# teiler10e7V3.net
KiCad netlist of a schematic drawn in EAGLE
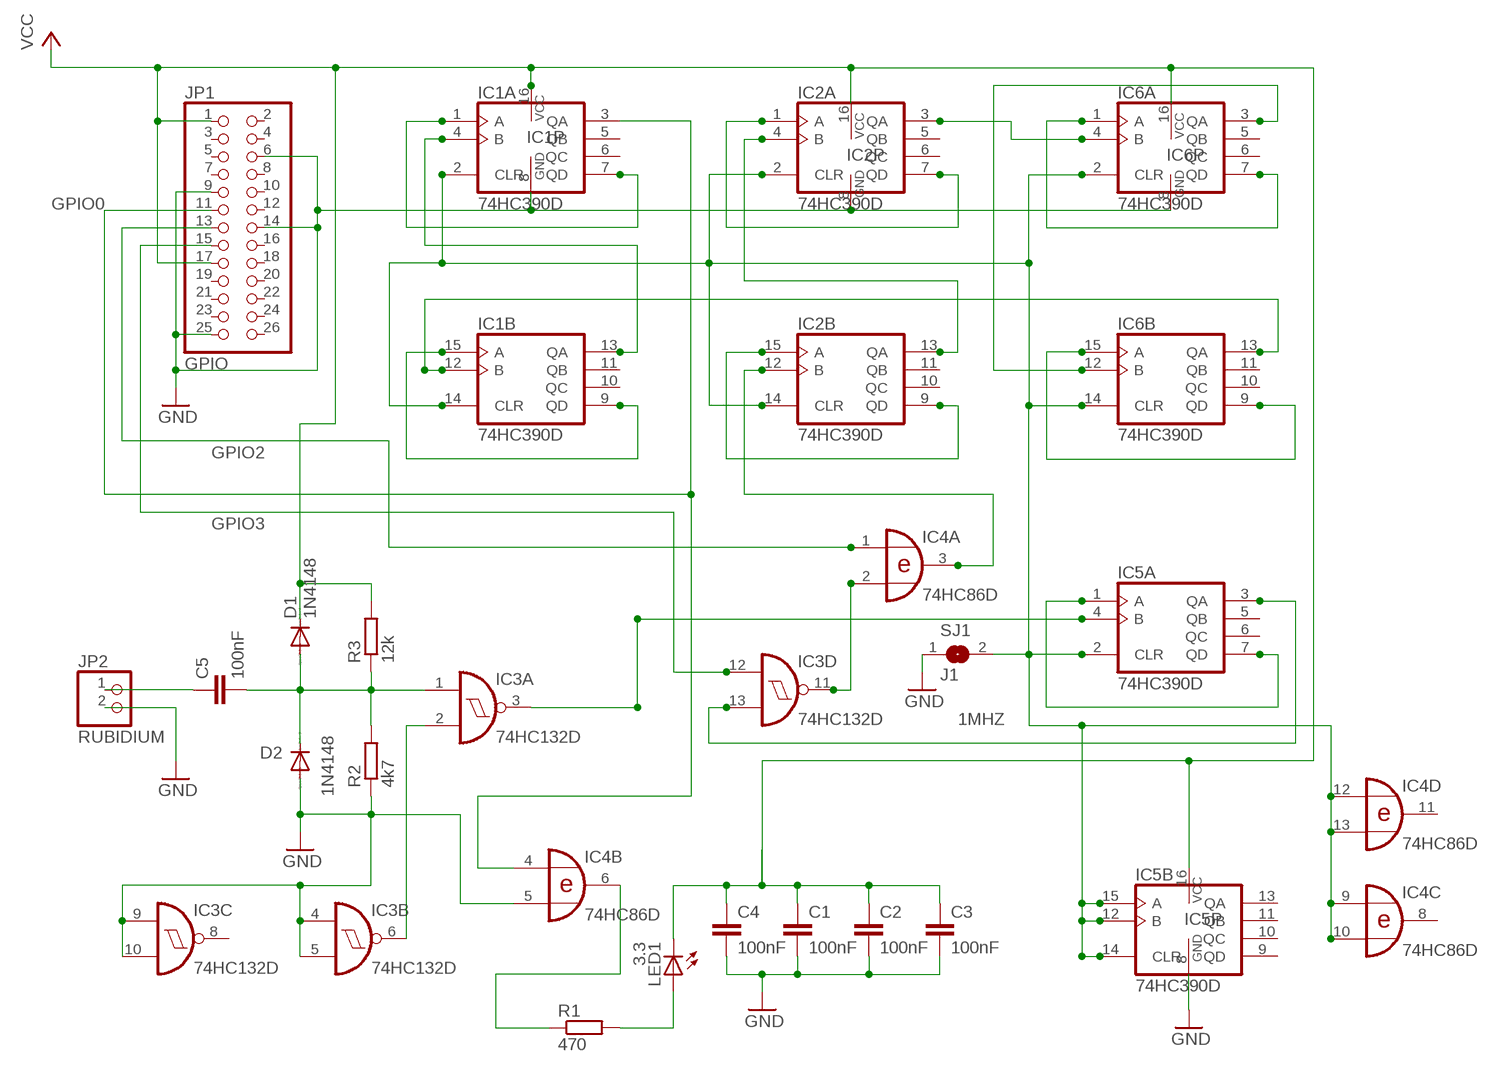
[diagram p0: schematic, sheet 1]

(export (version "E")
  (design (tool "Eeschema 10.0.6"))
  (components
    (comp (ref "C1")
      (value "100nF")
      (footprint "eagle-import:C025-025X050")
      (libsource (lib "eagle-import") (part "C-EU025-025X050"))
    )
    (comp (ref "C2")
      (value "100nF")
      (footprint "eagle-import:C025-025X050")
      (libsource (lib "eagle-import") (part "C-EU025-025X050"))
    )
    (comp (ref "C3")
      (value "100nF")
      (footprint "eagle-import:C025-025X050")
      (libsource (lib "eagle-import") (part "C-EU025-025X050"))
    )
    (comp (ref "C4")
      (value "100nF")
      (footprint "eagle-import:C025-025X050")
      (libsource (lib "eagle-import") (part "C-EU025-025X050"))
    )
    (comp (ref "C5")
      (value "100nF")
      (footprint "eagle-import:C025-025X050")
      (libsource (lib "eagle-import") (part "C-EU025-025X050"))
    )
    (comp (ref "D1")
      (value "1N4148")
      (footprint "eagle-import:DO35-7")
      (libsource (lib "eagle-import") (part "1N4148DO35-7"))
    )
    (comp (ref "D2")
      (value "1N4148")
      (footprint "eagle-import:DO35-7")
      (libsource (lib "eagle-import") (part "1N4148DO35-7"))
    )
    (comp (ref "IC1")
      (value "74HC390D")
      (footprint "eagle-import:SO16")
      (libsource (lib "eagle-import") (part "74390DHC"))
    )
    (comp (ref "IC2")
      (value "74HC390D")
      (footprint "eagle-import:SO16")
      (libsource (lib "eagle-import") (part "74390DHC"))
    )
    (comp (ref "IC3")
      (value "74HC132D")
      (footprint "eagle-import:SO14")
      (libsource (lib "eagle-import") (part "74132DHC"))
    )
    (comp (ref "IC4")
      (value "74HC86D")
      (footprint "eagle-import:SO14")
      (libsource (lib "eagle-import") (part "7486DHC"))
    )
    (comp (ref "IC5")
      (value "74HC390D")
      (footprint "eagle-import:SO16")
      (libsource (lib "eagle-import") (part "74390DHC"))
    )
    (comp (ref "IC6")
      (value "74HC390D")
      (footprint "eagle-import:SO16")
      (libsource (lib "eagle-import") (part "74390DHC"))
    )
    (comp (ref "JP1")
      (value "GPIO")
      (footprint "eagle-import:2X13")
      (libsource (lib "eagle-import") (part "PINHD-2X13"))
    )
    (comp (ref "JP2")
      (value "RUBIDIUM")
      (footprint "eagle-import:1X02_90")
      (libsource (lib "eagle-import") (part "PINHD-1X2/90"))
    )
    (comp (ref "LED1")
      (value "3.3")
      (footprint "eagle-import:LED3MM")
      (libsource (lib "eagle-import") (part "LED3MM"))
    )
    (comp (ref "R1")
      (value "470")
      (footprint "eagle-import:0207_10")
      (libsource (lib "eagle-import") (part "R-EU_0207/10"))
    )
    (comp (ref "R2")
      (value "4k7")
      (footprint "eagle-import:0207_10")
      (libsource (lib "eagle-import") (part "R-EU_0207/10"))
    )
    (comp (ref "R3")
      (value "12k")
      (footprint "eagle-import:0207_10")
      (libsource (lib "eagle-import") (part "R-EU_0207/10"))
    )
    (comp (ref "SJ1")
      (value "J1")
      (footprint "eagle-import:SJW")
      (libsource (lib "eagle-import") (part "SJW"))
    )
  )
  (nets
    (net (code "1") (name "/1MHZ") (class "Default")
      (node (ref "IC3") (pin "13") (pinfunction "I1_13") (pintype "input"))
      (node (ref "IC5") (pin "3") (pinfunction "QA_3") (pintype "output"))
    )
    (net (code "2") (name "/GPIO0") (class "Default")
      (node (ref "IC1") (pin "3") (pinfunction "QA_3") (pintype "output"))
      (node (ref "IC4") (pin "4") (pinfunction "I0_4") (pintype "input"))
      (node (ref "JP1") (pin "11") (pinfunction "11_11") (pintype "passive"))
    )
    (net (code "3") (name "/GPIO2") (class "Default")
      (node (ref "IC4") (pin "1") (pinfunction "I0_1") (pintype "input"))
      (node (ref "JP1") (pin "13") (pinfunction "13_13") (pintype "passive"))
    )
    (net (code "4") (name "/GPIO3") (class "Default")
      (node (ref "IC3") (pin "12") (pinfunction "I0_12") (pintype "input"))
      (node (ref "JP1") (pin "15") (pinfunction "15_15") (pintype "passive"))
    )
    (net (code "5") (name "GND") (class "Default")
      (node (ref "C1") (pin "2") (pinfunction "2_2") (pintype "passive"))
      (node (ref "C2") (pin "2") (pinfunction "2_2") (pintype "passive"))
      (node (ref "C3") (pin "2") (pinfunction "2_2") (pintype "passive"))
      (node (ref "C4") (pin "2") (pinfunction "2_2") (pintype "passive"))
      (node (ref "D2") (pin "A") (pinfunction "A_A") (pintype "passive"))
      (node (ref "IC1") (pin "8") (pinfunction "GND_8") (pintype "power_in"))
      (node (ref "IC2") (pin "8") (pinfunction "GND_8") (pintype "power_in"))
      (node (ref "IC3") (pin "10") (pinfunction "I1_10") (pintype "input"))
      (node (ref "IC3") (pin "4") (pinfunction "I0_4") (pintype "input"))
      (node (ref "IC3") (pin "5") (pinfunction "I1_5") (pintype "input"))
      (node (ref "IC3") (pin "9") (pinfunction "I0_9") (pintype "input"))
      (node (ref "IC4") (pin "5") (pinfunction "I1_5") (pintype "input"))
      (node (ref "IC5") (pin "8") (pinfunction "GND_8") (pintype "power_in"))
      (node (ref "IC6") (pin "8") (pinfunction "GND_8") (pintype "power_in"))
      (node (ref "JP1") (pin "14") (pinfunction "14_14") (pintype "passive"))
      (node (ref "JP1") (pin "25") (pinfunction "25_25") (pintype "passive"))
      (node (ref "JP1") (pin "6") (pinfunction "6_6") (pintype "passive"))
      (node (ref "JP1") (pin "9") (pinfunction "9_9") (pintype "passive"))
      (node (ref "JP2") (pin "2") (pinfunction "2_2") (pintype "passive"))
      (node (ref "R2") (pin "1") (pinfunction "1_1") (pintype "passive"))
      (node (ref "SJ1") (pin "1") (pinfunction "1_1") (pintype "passive"))
    )
    (net (code "6") (name "Net-(C5-Pad1)") (class "Default")
      (node (ref "C5") (pin "1") (pinfunction "1_1") (pintype "passive"))
      (node (ref "JP2") (pin "1") (pinfunction "1_1") (pintype "passive"))
    )
    (net (code "7") (name "Net-(IC1A-A)") (class "Default")
      (node (ref "IC1") (pin "1") (pinfunction "A_1") (pintype "input"))
      (node (ref "IC1") (pin "7") (pinfunction "QD_7") (pintype "output"))
    )
    (net (code "8") (name "Net-(IC1A-B)") (class "Default")
      (node (ref "IC1") (pin "13") (pinfunction "QA_13") (pintype "output"))
      (node (ref "IC1") (pin "4") (pinfunction "B_4") (pintype "input"))
    )
    (net (code "9") (name "Net-(IC1A-CLR)") (class "Default")
      (node (ref "IC1") (pin "14") (pinfunction "CLR_14") (pintype "input"))
      (node (ref "IC1") (pin "2") (pinfunction "CLR_2") (pintype "input"))
      (node (ref "IC2") (pin "14") (pinfunction "CLR_14") (pintype "input"))
      (node (ref "IC2") (pin "2") (pinfunction "CLR_2") (pintype "input"))
      (node (ref "IC4") (pin "10") (pinfunction "I1_10") (pintype "input"))
      (node (ref "IC4") (pin "12") (pinfunction "I0_12") (pintype "input"))
      (node (ref "IC4") (pin "13") (pinfunction "I1_13") (pintype "input"))
      (node (ref "IC4") (pin "9") (pinfunction "I0_9") (pintype "input"))
      (node (ref "IC5") (pin "12") (pinfunction "B_12") (pintype "input"))
      (node (ref "IC5") (pin "14") (pinfunction "CLR_14") (pintype "input"))
      (node (ref "IC5") (pin "15") (pinfunction "A_15") (pintype "input"))
      (node (ref "IC5") (pin "2") (pinfunction "CLR_2") (pintype "input"))
      (node (ref "IC6") (pin "14") (pinfunction "CLR_14") (pintype "input"))
      (node (ref "IC6") (pin "2") (pinfunction "CLR_2") (pintype "input"))
      (node (ref "SJ1") (pin "2") (pinfunction "2_2") (pintype "passive"))
    )
    (net (code "10") (name "Net-(IC1B-A)") (class "Default")
      (node (ref "IC1") (pin "15") (pinfunction "A_15") (pintype "input"))
      (node (ref "IC1") (pin "9") (pinfunction "QD_9") (pintype "output"))
    )
    (net (code "11") (name "Net-(IC1B-B)") (class "Default")
      (node (ref "IC1") (pin "12") (pinfunction "B_12") (pintype "input"))
      (node (ref "IC6") (pin "13") (pinfunction "QA_13") (pintype "output"))
    )
    (net (code "12") (name "Net-(IC2A-A)") (class "Default")
      (node (ref "IC2") (pin "1") (pinfunction "A_1") (pintype "input"))
      (node (ref "IC2") (pin "7") (pinfunction "QD_7") (pintype "output"))
    )
    (net (code "13") (name "Net-(IC2A-B)") (class "Default")
      (node (ref "IC2") (pin "13") (pinfunction "QA_13") (pintype "output"))
      (node (ref "IC2") (pin "4") (pinfunction "B_4") (pintype "input"))
    )
    (net (code "14") (name "Net-(IC2A-QA)") (class "Default")
      (node (ref "IC2") (pin "3") (pinfunction "QA_3") (pintype "output"))
      (node (ref "IC6") (pin "4") (pinfunction "B_4") (pintype "input"))
    )
    (net (code "15") (name "Net-(IC2B-A)") (class "Default")
      (node (ref "IC2") (pin "15") (pinfunction "A_15") (pintype "input"))
      (node (ref "IC2") (pin "9") (pinfunction "QD_9") (pintype "output"))
    )
    (net (code "16") (name "Net-(IC2B-B)") (class "Default")
      (node (ref "IC2") (pin "12") (pinfunction "B_12") (pintype "input"))
      (node (ref "IC4") (pin "3") (pinfunction "O_3") (pintype "output"))
    )
    (net (code "17") (name "Net-(IC3A-I0)") (class "Default")
      (node (ref "C5") (pin "2") (pinfunction "2_2") (pintype "passive"))
      (node (ref "D1") (pin "A") (pinfunction "A_A") (pintype "passive"))
      (node (ref "D2") (pin "C") (pinfunction "C_C") (pintype "passive"))
      (node (ref "IC3") (pin "1") (pinfunction "I0_1") (pintype "input"))
      (node (ref "R2") (pin "2") (pinfunction "2_2") (pintype "passive"))
      (node (ref "R3") (pin "1") (pinfunction "1_1") (pintype "passive"))
    )
    (net (code "18") (name "Net-(IC3A-I1)") (class "Default")
      (node (ref "IC3") (pin "2") (pinfunction "I1_2") (pintype "input"))
      (node (ref "IC3") (pin "6") (pinfunction "O_6") (pintype "output"))
    )
    (net (code "19") (name "Net-(IC3A-O)") (class "Default")
      (node (ref "IC3") (pin "3") (pinfunction "O_3") (pintype "output"))
      (node (ref "IC5") (pin "4") (pinfunction "B_4") (pintype "input"))
    )
    (net (code "20") (name "Net-(IC3D-O)") (class "Default")
      (node (ref "IC3") (pin "11") (pinfunction "O_11") (pintype "output"))
      (node (ref "IC4") (pin "2") (pinfunction "I1_2") (pintype "input"))
    )
    (net (code "21") (name "Net-(IC4B-O)") (class "Default")
      (node (ref "IC4") (pin "6") (pinfunction "O_6") (pintype "output"))
      (node (ref "R1") (pin "1") (pinfunction "1_1") (pintype "passive"))
    )
    (net (code "22") (name "Net-(IC5A-A)") (class "Default")
      (node (ref "IC5") (pin "1") (pinfunction "A_1") (pintype "input"))
      (node (ref "IC5") (pin "7") (pinfunction "QD_7") (pintype "output"))
    )
    (net (code "23") (name "Net-(IC6A-A)") (class "Default")
      (node (ref "IC6") (pin "1") (pinfunction "A_1") (pintype "input"))
      (node (ref "IC6") (pin "7") (pinfunction "QD_7") (pintype "output"))
    )
    (net (code "24") (name "Net-(IC6A-QA)") (class "Default")
      (node (ref "IC6") (pin "12") (pinfunction "B_12") (pintype "input"))
      (node (ref "IC6") (pin "3") (pinfunction "QA_3") (pintype "output"))
    )
    (net (code "25") (name "Net-(IC6B-A)") (class "Default")
      (node (ref "IC6") (pin "15") (pinfunction "A_15") (pintype "input"))
      (node (ref "IC6") (pin "9") (pinfunction "QD_9") (pintype "output"))
    )
    (net (code "26") (name "Net-(LED1-PadA)") (class "Default")
      (node (ref "LED1") (pin "A") (pinfunction "A_A") (pintype "passive"))
      (node (ref "R1") (pin "2") (pinfunction "2_2") (pintype "passive"))
    )
    (net (code "27") (name "VCC") (class "Default")
      (node (ref "C1") (pin "1") (pinfunction "1_1") (pintype "passive"))
      (node (ref "C2") (pin "1") (pinfunction "1_1") (pintype "passive"))
      (node (ref "C3") (pin "1") (pinfunction "1_1") (pintype "passive"))
      (node (ref "C4") (pin "1") (pinfunction "1_1") (pintype "passive"))
      (node (ref "D1") (pin "C") (pinfunction "C_C") (pintype "passive"))
      (node (ref "IC1") (pin "16") (pinfunction "VCC_16") (pintype "power_in"))
      (node (ref "IC2") (pin "16") (pinfunction "VCC_16") (pintype "power_in"))
      (node (ref "IC5") (pin "16") (pinfunction "VCC_16") (pintype "power_in"))
      (node (ref "IC6") (pin "16") (pinfunction "VCC_16") (pintype "power_in"))
      (node (ref "JP1") (pin "1") (pinfunction "1_1") (pintype "passive"))
      (node (ref "JP1") (pin "17") (pinfunction "17_17") (pintype "passive"))
      (node (ref "LED1") (pin "K") (pinfunction "C_K") (pintype "passive"))
      (node (ref "R3") (pin "2") (pinfunction "2_2") (pintype "passive"))
    )
    (net (code "28") (name "unconnected-(IC1A-QB-Pad5)") (class "Default")
      (node (ref "IC1") (pin "5") (pinfunction "QB_5") (pintype "output"))
    )
    (net (code "29") (name "unconnected-(IC1A-QC-Pad6)") (class "Default")
      (node (ref "IC1") (pin "6") (pinfunction "QC_6") (pintype "output"))
    )
    (net (code "30") (name "unconnected-(IC1B-QB-Pad11)") (class "Default")
      (node (ref "IC1") (pin "11") (pinfunction "QB_11") (pintype "output"))
    )
    (net (code "31") (name "unconnected-(IC1B-QC-Pad10)") (class "Default")
      (node (ref "IC1") (pin "10") (pinfunction "QC_10") (pintype "output"))
    )
    (net (code "32") (name "unconnected-(IC2A-QB-Pad5)") (class "Default")
      (node (ref "IC2") (pin "5") (pinfunction "QB_5") (pintype "output"))
    )
    (net (code "33") (name "unconnected-(IC2A-QC-Pad6)") (class "Default")
      (node (ref "IC2") (pin "6") (pinfunction "QC_6") (pintype "output"))
    )
    (net (code "34") (name "unconnected-(IC2B-QB-Pad11)") (class "Default")
      (node (ref "IC2") (pin "11") (pinfunction "QB_11") (pintype "output"))
    )
    (net (code "35") (name "unconnected-(IC2B-QC-Pad10)") (class "Default")
      (node (ref "IC2") (pin "10") (pinfunction "QC_10") (pintype "output"))
    )
    (net (code "36") (name "unconnected-(IC3C-O-Pad8)") (class "Default")
      (node (ref "IC3") (pin "8") (pinfunction "O_8") (pintype "output"))
    )
    (net (code "37") (name "unconnected-(IC4C-O-Pad8)") (class "Default")
      (node (ref "IC4") (pin "8") (pinfunction "O_8") (pintype "output"))
    )
    (net (code "38") (name "unconnected-(IC4D-O-Pad11)") (class "Default")
      (node (ref "IC4") (pin "11") (pinfunction "O_11") (pintype "output"))
    )
    (net (code "39") (name "unconnected-(IC5A-QB-Pad5)") (class "Default")
      (node (ref "IC5") (pin "5") (pinfunction "QB_5") (pintype "output"))
    )
    (net (code "40") (name "unconnected-(IC5A-QC-Pad6)") (class "Default")
      (node (ref "IC5") (pin "6") (pinfunction "QC_6") (pintype "output"))
    )
    (net (code "41") (name "unconnected-(IC5B-QA-Pad13)") (class "Default")
      (node (ref "IC5") (pin "13") (pinfunction "QA_13") (pintype "output"))
    )
    (net (code "42") (name "unconnected-(IC5B-QB-Pad11)") (class "Default")
      (node (ref "IC5") (pin "11") (pinfunction "QB_11") (pintype "output"))
    )
    (net (code "43") (name "unconnected-(IC5B-QC-Pad10)") (class "Default")
      (node (ref "IC5") (pin "10") (pinfunction "QC_10") (pintype "output"))
    )
    (net (code "44") (name "unconnected-(IC5B-QD-Pad9)") (class "Default")
      (node (ref "IC5") (pin "9") (pinfunction "QD_9") (pintype "output"))
    )
    (net (code "45") (name "unconnected-(IC6A-QB-Pad5)") (class "Default")
      (node (ref "IC6") (pin "5") (pinfunction "QB_5") (pintype "output"))
    )
    (net (code "46") (name "unconnected-(IC6A-QC-Pad6)") (class "Default")
      (node (ref "IC6") (pin "6") (pinfunction "QC_6") (pintype "output"))
    )
    (net (code "47") (name "unconnected-(IC6B-QB-Pad11)") (class "Default")
      (node (ref "IC6") (pin "11") (pinfunction "QB_11") (pintype "output"))
    )
    (net (code "48") (name "unconnected-(IC6B-QC-Pad10)") (class "Default")
      (node (ref "IC6") (pin "10") (pinfunction "QC_10") (pintype "output"))
    )
    (net (code "49") (name "unconnected-(JP1-Pad2)") (class "Default")
      (node (ref "JP1") (pin "2") (pinfunction "2_2") (pintype "passive"))
    )
    (net (code "50") (name "unconnected-(JP1-Pad3)") (class "Default")
      (node (ref "JP1") (pin "3") (pinfunction "3_3") (pintype "passive"))
    )
    (net (code "51") (name "unconnected-(JP1-Pad4)") (class "Default")
      (node (ref "JP1") (pin "4") (pinfunction "4_4") (pintype "passive"))
    )
    (net (code "52") (name "unconnected-(JP1-Pad5)") (class "Default")
      (node (ref "JP1") (pin "5") (pinfunction "5_5") (pintype "passive"))
    )
    (net (code "53") (name "unconnected-(JP1-Pad7)") (class "Default")
      (node (ref "JP1") (pin "7") (pinfunction "7_7") (pintype "passive"))
    )
    (net (code "54") (name "unconnected-(JP1-Pad8)") (class "Default")
      (node (ref "JP1") (pin "8") (pinfunction "8_8") (pintype "passive"))
    )
    (net (code "55") (name "unconnected-(JP1-Pad10)") (class "Default")
      (node (ref "JP1") (pin "10") (pinfunction "10_10") (pintype "passive"))
    )
    (net (code "56") (name "unconnected-(JP1-Pad12)") (class "Default")
      (node (ref "JP1") (pin "12") (pinfunction "12_12") (pintype "passive"))
    )
    (net (code "57") (name "unconnected-(JP1-Pad16)") (class "Default")
      (node (ref "JP1") (pin "16") (pinfunction "16_16") (pintype "passive"))
    )
    (net (code "58") (name "unconnected-(JP1-Pad18)") (class "Default")
      (node (ref "JP1") (pin "18") (pinfunction "18_18") (pintype "passive"))
    )
    (net (code "59") (name "unconnected-(JP1-Pad19)") (class "Default")
      (node (ref "JP1") (pin "19") (pinfunction "19_19") (pintype "passive"))
    )
    (net (code "60") (name "unconnected-(JP1-Pad20)") (class "Default")
      (node (ref "JP1") (pin "20") (pinfunction "20_20") (pintype "passive"))
    )
    (net (code "61") (name "unconnected-(JP1-Pad21)") (class "Default")
      (node (ref "JP1") (pin "21") (pinfunction "21_21") (pintype "passive"))
    )
    (net (code "62") (name "unconnected-(JP1-Pad22)") (class "Default")
      (node (ref "JP1") (pin "22") (pinfunction "22_22") (pintype "passive"))
    )
    (net (code "63") (name "unconnected-(JP1-Pad23)") (class "Default")
      (node (ref "JP1") (pin "23") (pinfunction "23_23") (pintype "passive"))
    )
    (net (code "64") (name "unconnected-(JP1-Pad24)") (class "Default")
      (node (ref "JP1") (pin "24") (pinfunction "24_24") (pintype "passive"))
    )
    (net (code "65") (name "unconnected-(JP1-Pad26)") (class "Default")
      (node (ref "JP1") (pin "26") (pinfunction "26_26") (pintype "passive"))
    )
  )
)
